# Alimentation.net
KiCad netlist of a schematic drawn in Altium Designer
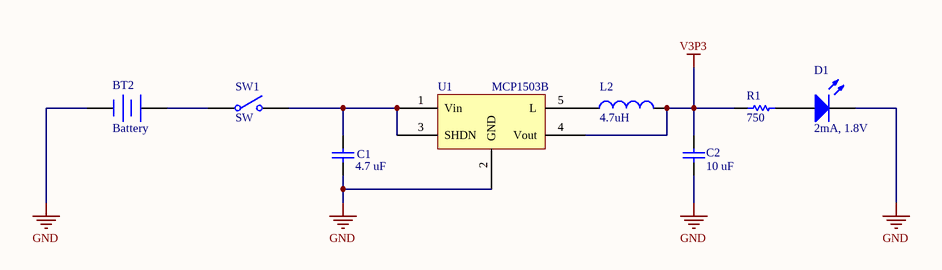
[diagram p0: Alimentation.SchDoc]

(export (version "E")
  (design (tool "Eeschema 10.0.6"))
  (components
    (comp (ref "BT2")
      (value "Battery")
      (footprint "Battery Holder")
      (description "Multicell Battery")
      (libsource (lib "Miscellaneous Devices") (part "Battery"))
    )
    (comp (ref "C1")
      (value "4.7 uF")
      (footprint "CAP 0603")
      (description "Capacitor")
      (libsource (lib "Miscellaneous Devices") (part "Cap"))
    )
    (comp (ref "C2")
      (value "10 uF")
      (footprint "CAP 0603")
      (description "Capacitor")
      (libsource (lib "Miscellaneous Devices") (part "Cap"))
    )
    (comp (ref "D1")
      (value "2mA, 1.8V")
      (footprint "LED")
      (description "Typical INFRARED GaAs LED")
      (libsource (lib "Miscellaneous Devices") (part "LED0"))
    )
    (comp (ref "L2")
      (value "4.7uH")
      (footprint "Coil")
      (description "Inductor")
      (libsource (lib "Miscellaneous Devices") (part "Inductor"))
    )
    (comp (ref "R1")
      (value "750")
      (footprint "RES 0603")
      (description "Resistor")
      (libsource (lib "Miscellaneous Devices") (part "Res1"))
    )
    (comp (ref "SW1")
      (value "SW")
      (footprint "SWITCH ON/OFF")
      (description "Single-Pole, Single-Throw Switch")
      (libsource (lib "Miscellaneous Devices") (part "SW-SPST"))
    )
    (comp (ref "U1")
      (value "MCP1503B")
      (footprint "MCP1603B/TSOT")
      (description "Fixed 3.3Vout 0.5Aout regulator")
      (libsource (lib "Schematics_Library") (part "MCP1603B"))
    )
  )
  (nets
    (net (code "1") (name "GND") (class "Default")
      (node (ref "BT2") (pin "2") (pinfunction "-_2") (pintype "passive"))
      (node (ref "C1") (pin "1") (pinfunction "1_1") (pintype "passive"))
      (node (ref "C2") (pin "1") (pinfunction "1_1") (pintype "passive"))
      (node (ref "D1") (pin "2") (pinfunction "K_2") (pintype "passive"))
      (node (ref "U1") (pin "2") (pinfunction "GND_2") (pintype "passive"))
    )
    (net (code "2") (name "Net-(BT2-+)") (class "Default")
      (node (ref "BT2") (pin "1") (pinfunction "+_1") (pintype "passive"))
      (node (ref "SW1") (pin "1") (pinfunction "COMMON_1") (pintype "passive"))
    )
    (net (code "3") (name "Net-(D1-A)") (class "Default")
      (node (ref "D1") (pin "1") (pinfunction "A_1") (pintype "passive"))
      (node (ref "R1") (pin "1") (pinfunction "1_1") (pintype "passive"))
    )
    (net (code "4") (name "Net-(SW1-NO)") (class "Default")
      (node (ref "C1") (pin "2") (pinfunction "2_2") (pintype "passive"))
      (node (ref "SW1") (pin "2") (pinfunction "NO_2") (pintype "passive"))
      (node (ref "U1") (pin "1") (pinfunction "Vin_1") (pintype "passive"))
      (node (ref "U1") (pin "3") (pinfunction "SHDN_3") (pintype "passive"))
    )
    (net (code "5") (name "Net-(U1-L)") (class "Default")
      (node (ref "L2") (pin "1") (pinfunction "1_1") (pintype "passive"))
      (node (ref "U1") (pin "5") (pinfunction "L_5") (pintype "passive"))
    )
    (net (code "6") (name "V3P3") (class "Default")
      (node (ref "C2") (pin "2") (pinfunction "2_2") (pintype "passive"))
      (node (ref "L2") (pin "2") (pinfunction "2_2") (pintype "passive"))
      (node (ref "R1") (pin "2") (pinfunction "2_2") (pintype "passive"))
      (node (ref "U1") (pin "4") (pinfunction "Vout_4") (pintype "passive"))
    )
  )
)
